# POWER_GEN.net
KiCad netlist of a schematic drawn in Altium Designer
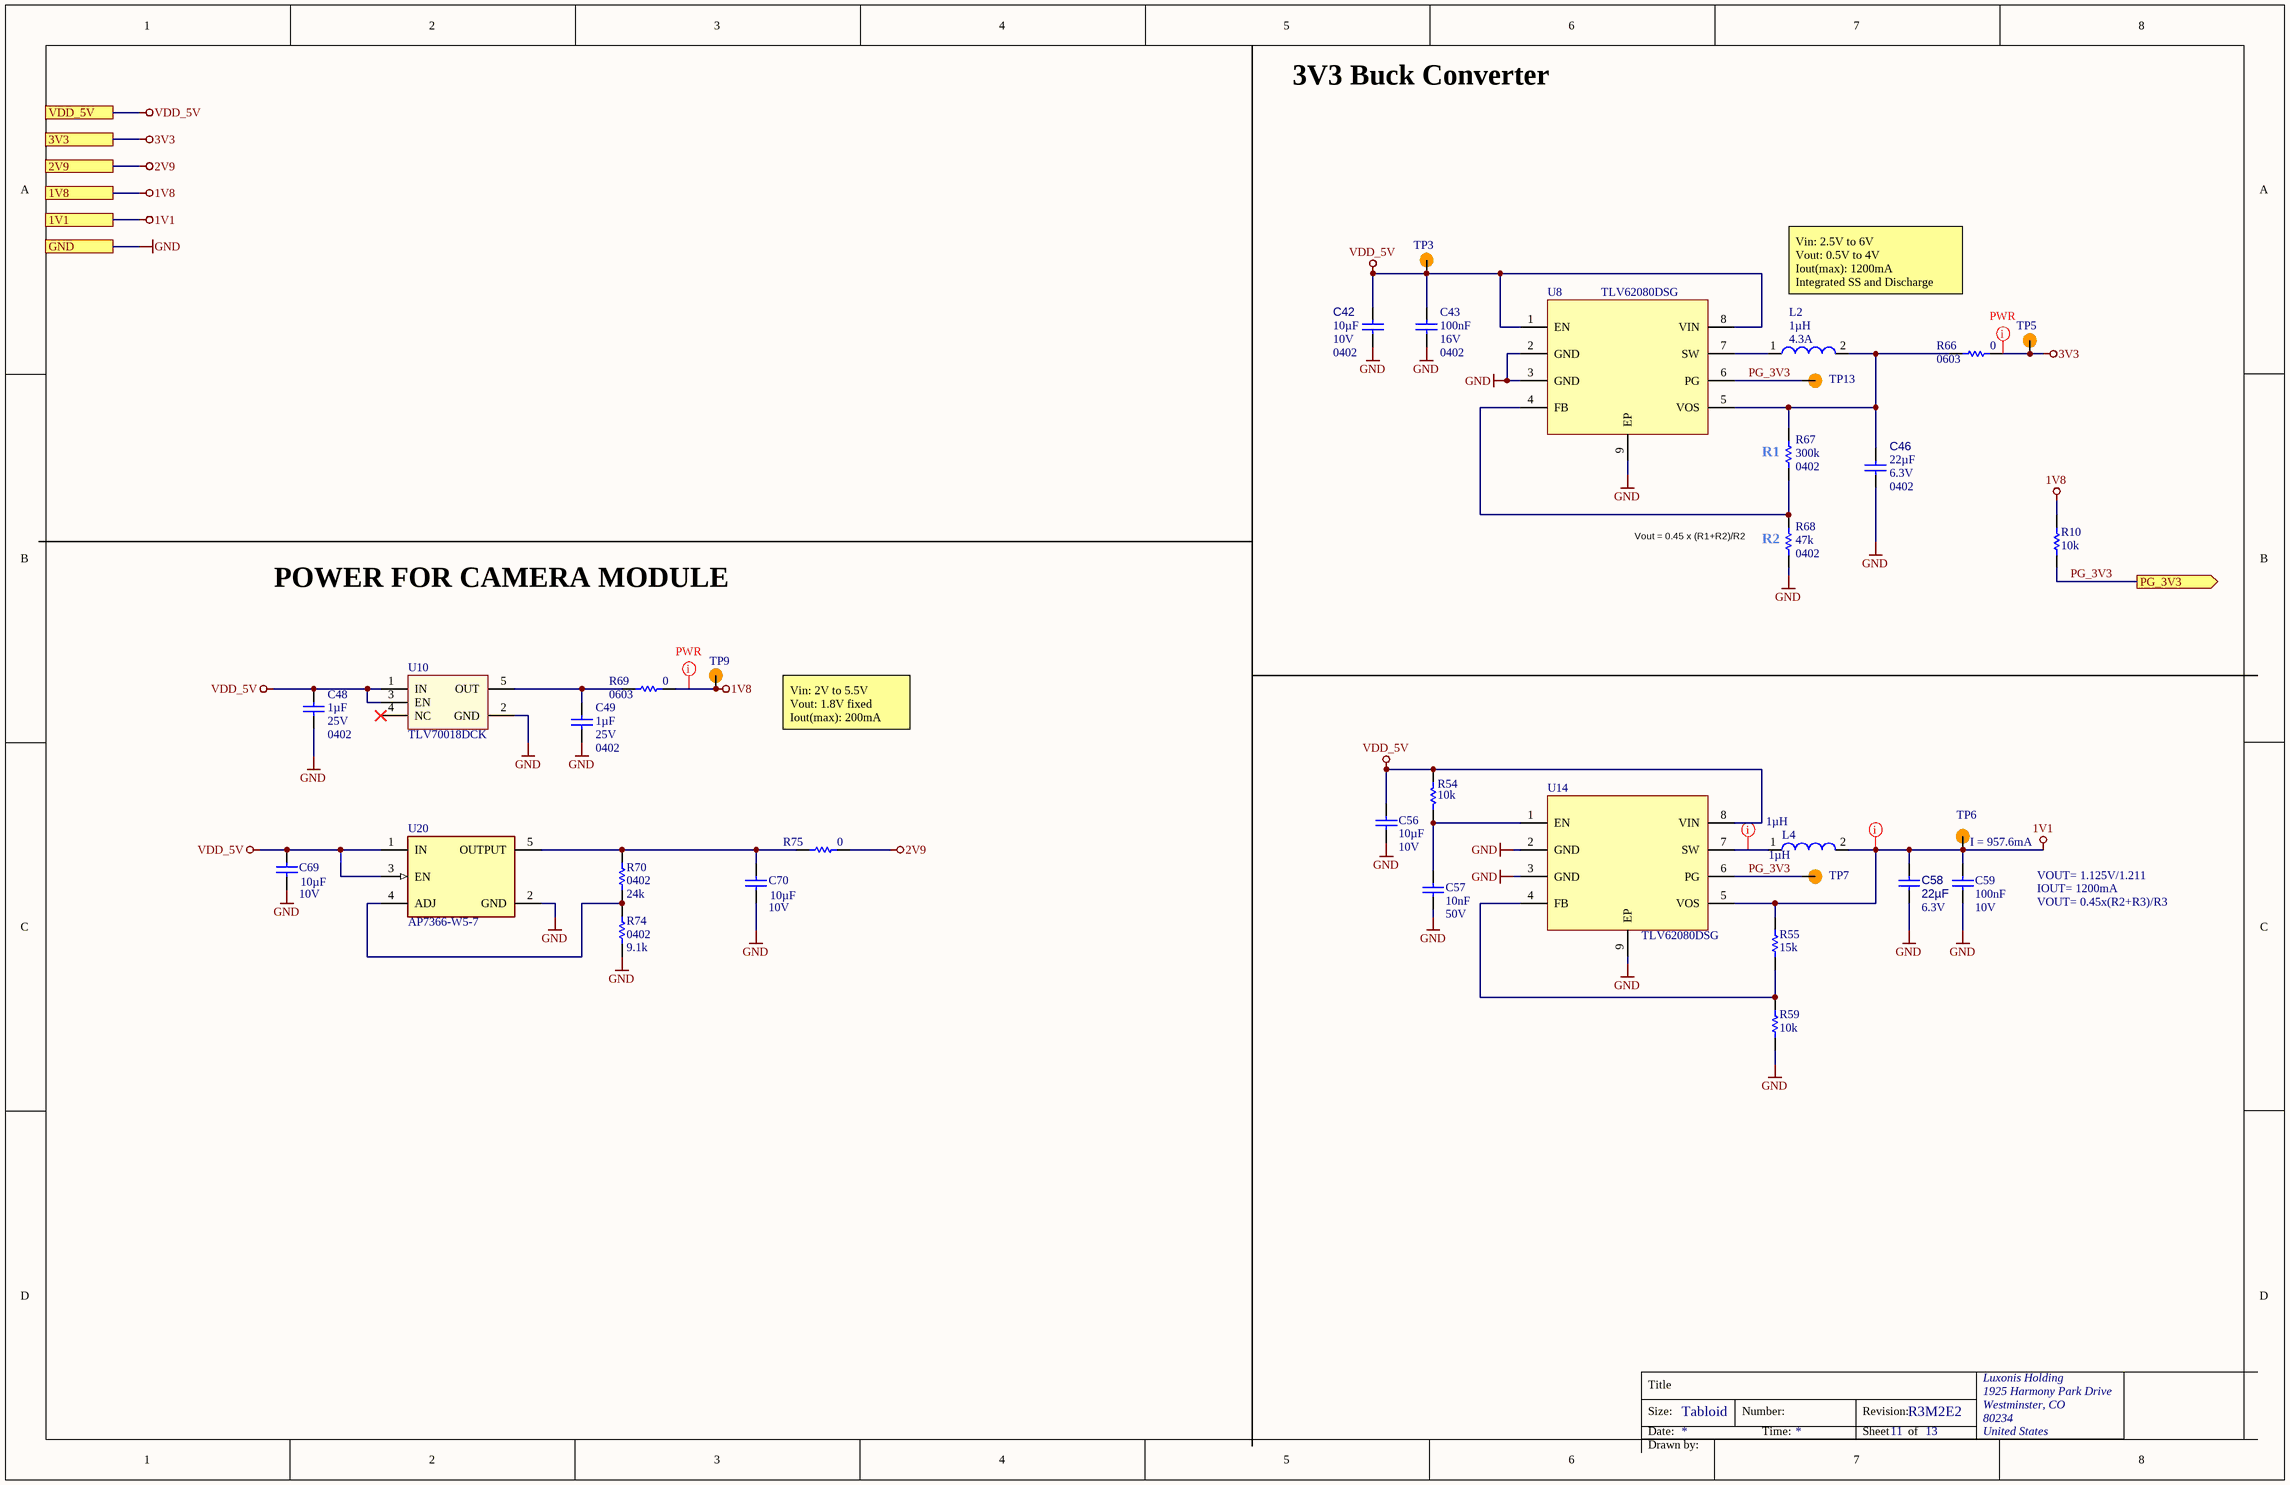
[diagram p0: POWER_GEN.SchDoc]

(export (version "E")
  (design (tool "Eeschema 10.0.6"))
  (components
    (comp (ref "C42")
      (value "10µF")
      (footprint "CAPC0402(1005)60_L")
      (description "CAP CER 10UF 10V X5R 0402 20%")
      (fields
        (field (name "VOLTAGE RATING") "10V")
        (field (name "TOLERANCE") "20%")
        (field (name "CASE/PACKAGE") "0402")
        (field (name "Comment") "GRM155R61A106ME11D")
      )
      (libsource (lib "Luxonis LLC") (part "*"))
    )
    (comp (ref "C43")
      (value "100nF")
      (footprint "CAPC0402(1005)60_N")
      (description "CAP CER 0.1UF 16V X7R 0402 10%")
      (fields
        (field (name "VOLTAGE RATING") "16V")
        (field (name "CASE/PACKAGE") "0402")
        (field (name "TOLERANCE") "10%")
        (field (name "Comment") "CL05B104KO5NFNC")
      )
      (libsource (lib "Luxonis LLC") (part "GRM188R61C475KAAJD"))
    )
    (comp (ref "C46")
      (value "22µF")
      (footprint "CAPC0402(1005)60_L")
      (description "CAP CER 22UF 6.3V X5R 0402 20%")
      (fields
        (field (name "VOLTAGE RATING") "6.3V")
        (field (name "CASE/PACKAGE") "0402")
        (field (name "TOLERANCE") "20%")
        (field (name "Comment") "CL05A226MQ5N6J8")
      )
      (libsource (lib "Luxonis LLC") (part "*"))
    )
    (comp (ref "C48")
      (value "1µF")
      (footprint "CAPC0402(1005)70_N")
      (description "CAP CER 1UF 25V X5R 0402 10%")
      (fields
        (field (name "VOLTAGE RATING") "25V")
        (field (name "CASE/PACKAGE") "0402")
        (field (name "TOLERANCE") "10%")
        (field (name "Comment") "GRM155R61E105KA12D")
      )
      (libsource (lib "Luxonis LLC") (part "GRM188R61C475KAAJD"))
    )
    (comp (ref "C49")
      (value "1µF")
      (footprint "CAPC0402(1005)70_N")
      (description "CAP CER 1UF 25V X5R 0402 10%")
      (fields
        (field (name "VOLTAGE RATING") "25V")
        (field (name "CASE/PACKAGE") "0402")
        (field (name "TOLERANCE") "10%")
        (field (name "Comment") "GRM155R61E105KA12D")
      )
      (libsource (lib "Luxonis LLC") (part "GRM188R61C475KAAJD"))
    )
    (comp (ref "C56")
      (value "10µF")
      (footprint "CAPC0603(1608)100_L")
      (description "CAP CER 10UF 10V X5R 0603 20%")
      (fields (field (name "TOLERANCE") "20%") (field (name "VOLTAGE RATING") "10V"))
      (libsource (lib "Luxonis LLC") (part "LLL153C70G474ME17E"))
    )
    (comp (ref "C57")
      (value "10nF")
      (footprint "CAPC0402(1005)60_L")
      (description "CAP CER 10000PF 50V X7R 0402 10%")
      (fields (field (name "TOLERANCE") "10%") (field (name "VOLTAGE RATING") "50V"))
      (libsource (lib "Luxonis LLC") (part "GRM188R61C475KAAJD"))
    )
    (comp (ref "C58")
      (value "22µF")
      (footprint "CAPC0402(1005)60_L")
      (description "CAP CER 22UF 6.3V X5R 0402 20%")
      (fields (field (name "TOLERANCE") "20%") (field (name "VOLTAGE RATING") "6.3V"))
      (libsource (lib "Luxonis LLC") (part "*"))
    )
    (comp (ref "C59")
      (value "100nF")
      (footprint "CAPC0402(1005)70_L")
      (description "CAP CER 0.1UF 10V X7R 0402 5%")
      (fields (field (name "TOLERANCE") "5%") (field (name "VOLTAGE RATING") "10V"))
      (libsource (lib "Luxonis LLC") (part "GRM188R61C475KAAJD"))
    )
    (comp (ref "C69")
      (value "10µF")
      (footprint "CAPC0603(1608)100_L")
      (description "CAP CER 10UF 10V X5R 0603 20%")
      (fields
        (field (name "TOLERANCE") "20%")
        (field (name "VOLTAGE RATING") "10V")
        (field (name "Comment") "GRM188R61A106ME69D")
      )
      (libsource (lib "Luxonis LLC") (part "LLL153C70G474ME17E"))
    )
    (comp (ref "C70")
      (value "10µF")
      (footprint "CAPC0603(1608)100_L")
      (description "CAP CER 10UF 10V X5R 0603 20%")
      (fields
        (field (name "TOLERANCE") "20%")
        (field (name "VOLTAGE RATING") "10V")
        (field (name "Comment") "GRM188R61A106ME69D")
      )
      (libsource (lib "Luxonis LLC") (part "LLL153C70G474ME17E"))
    )
    (comp (ref "L2")
      (value "1µH")
      (footprint "DFE252012P-1R0M=P2")
      (description "FIXED IND 1UH 3.2A 42 MOHM SMD")
      (fields
        (field (name "MANUFACTURER") "Murata")
        (field (name "MANUFACTURER PART NUMBER") "DFE252012P-1R0M=P2")
        (field (name "CURRENT RATING") "4.3A")
      )
      (libsource (lib "Luxonis LLC") (part "DFE252012P-1R0M=P2"))
    )
    (comp (ref "L4")
      (value "1µH")
      (footprint "DFE252012P-1R0M=P2")
      (description "FIXED IND 1UH 3.2A 42 MOHM SMD")
      (fields
        (field (name "TOLERANCE") "20%")
        (field (name "MANUFACTURER") "Murata")
        (field (name "ALTIUM_VALUE") "1µH")
      )
      (libsource (lib "Luxonis LLC") (part "DFE252012P-1R0M=P2"))
    )
    (comp (ref "R10")
      (value "10k")
      (footprint "RESC0402(1005)_L")
      (description "RES SMD 10K OHM 1% 1/16W 0402")
      (fields (field (name "TOLERANCE") "1%"))
      (libsource (lib "Luxonis LLC") (part "RC0402FR-0722RL_1"))
    )
    (comp (ref "R54")
      (value "10k")
      (footprint "RESC0402(1005)_L")
      (description "RES SMD 10K OHM 1% 1/16W 0402")
      (fields (field (name "TOLERANCE") "1%"))
      (libsource (lib "Luxonis LLC") (part "RC0402FR-0722RL_1"))
    )
    (comp (ref "R55")
      (value "15k")
      (footprint "RESC0402(1005)_L")
      (description "RES SMD 15K OHM 1% 1/16W 0402")
      (fields (field (name "TOLERANCE") "1%"))
      (libsource (lib "Luxonis LLC") (part "Default resistor symbol"))
    )
    (comp (ref "R59")
      (value "10k")
      (footprint "RESC0402(1005)_L")
      (description "RES SMD 10K OHM 1% 1/16W 0402")
      (fields (field (name "TOLERANCE") "1%"))
      (libsource (lib "Luxonis LLC") (part "RC0402FR-0722RL_1"))
    )
    (comp (ref "R66")
      (value "0")
      (footprint "RESC0603(1608)_N")
      (description "RES SMD 0 OHM 5% 1/10W 0603")
      (fields
        (field (name "TOLERANCE") "5%")
        (field (name "CASE/PACKAGE") "0603")
        (field (name "Comment") "CRCW06030000Z0EA")
      )
      (libsource (lib "Luxonis LLC") (part "RC0402FR-0722RL_1"))
    )
    (comp (ref "R67")
      (value "300k")
      (footprint "RESC0402(1005)_N")
      (description "RES SMD 300K OHM 1% 1/16W 0402")
      (fields
        (field (name "CASE/PACKAGE") "0402")
        (field (name "TOLERANCE") "1%")
        (field (name "Comment") "RC0402FR-07300KL")
      )
      (libsource (lib "Luxonis LLC") (part "Default resistor symbol"))
    )
    (comp (ref "R68")
      (value "47k")
      (footprint "RESC0402(1005)_L")
      (description "RES SMD 47K OHM 1% 1/16W 0402")
      (fields
        (field (name "CASE/PACKAGE") "0402")
        (field (name "TOLERANCE") "1%")
        (field (name "Comment") "RC0402FR-0747KL")
      )
      (libsource (lib "Luxonis LLC") (part "Default resistor symbol"))
    )
    (comp (ref "R69")
      (value "0")
      (footprint "RESC0603(1608)_N")
      (description "RES SMD 0 OHM 5% 1/10W 0603")
      (fields
        (field (name "TOLERANCE") "5%")
        (field (name "CASE/PACKAGE") "0603")
        (field (name "Comment") "CRCW06030000Z0EA")
      )
      (libsource (lib "Luxonis LLC") (part "RC0402FR-0722RL_1"))
    )
    (comp (ref "R70")
      (value "24k")
      (footprint "RESC0402(1005)_L")
      (description "RES SMD 24K OHM 1% 1/16W 0402")
      (fields
        (field (name "CASE/PACKAGE") "0402")
        (field (name "TOLERANCE") "1%")
        (field (name "Comment") "RC0402FR-0724KL")
      )
      (libsource (lib "Luxonis LLC") (part "Default resistor symbol"))
    )
    (comp (ref "R74")
      (value "9.1k")
      (footprint "RESC0402(1005)_L")
      (description "RES SMD 9.1K OHM 1% 1/16W 0402")
      (fields
        (field (name "CASE/PACKAGE") "0402")
        (field (name "POWER") "63mW")
        (field (name "TOLERANCE") "1%")
      )
      (libsource (lib "Luxonis LLC") (part "Default resistor symbol"))
    )
    (comp (ref "R75")
      (value "0")
      (footprint "RESC0603(1608)_N")
      (description "RES SMD 0 OHM 5% 1/10W 0603")
      (fields (field (name "TOLERANCE") "5%") (field (name "Comment") "CRCW06030000Z0EA"))
      (libsource (lib "Luxonis LLC") (part "RC0402FR-0722RL_1"))
    )
    (comp (ref "TP3")
      (value "TEST_POINT")
      (footprint "TP075_150_NS")
      (libsource (lib "Luxonis LLC") (part "TEST_POINT"))
    )
    (comp (ref "TP5")
      (value "TEST_POINT")
      (footprint "TP075_150_NS")
      (libsource (lib "Luxonis LLC") (part "TEST_POINT"))
    )
    (comp (ref "TP6")
      (value "TEST_POINT")
      (footprint "TP075_150_NS")
      (libsource (lib "Luxonis LLC") (part "TEST_POINT"))
    )
    (comp (ref "TP7")
      (value "TEST_POINT")
      (footprint "TP075_150_NS")
      (libsource (lib "Luxonis LLC") (part "TEST_POINT"))
    )
    (comp (ref "TP9")
      (value "TEST_POINT")
      (footprint "TP075_150_NS")
      (libsource (lib "Luxonis LLC") (part "TEST_POINT"))
    )
    (comp (ref "TP13")
      (value "TEST_POINT")
      (footprint "TP075_150_NS")
      (libsource (lib "Luxonis LLC") (part "TEST_POINT"))
    )
    (comp (ref "U8")
      (value "TLV62080DSG")
      (footprint "TLV62080DSG")
      (description "IC REG BUCK ADJ 1.2A SYNC 8WSON")
      (libsource (lib "Luxonis LLC") (part "TLV62080DSG"))
    )
    (comp (ref "U10")
      (value "TLV70018DCK")
      (footprint "TLV70018DCK")
      (description "IC REG LINEAR 1.8V 200MA SC70-5 Linear Voltage Regulator IC  1 Output  200mA SC-70-5")
      (libsource (lib "Luxonis LLC") (part "TLV70018DCK"))
    )
    (comp (ref "U14")
      (value "TLV62080DSG")
      (footprint "TLV62080DSG")
      (description "IC REG BUCK ADJ 1.2A SYNC 8WSON")
      (libsource (lib "Luxonis LLC") (part "TLV62080DSG"))
    )
    (comp (ref "U20")
      (value "AP7366-W5-7")
      (footprint "FP-SOT25-MFG")
      (description "Adjustable Positive LDO Regulator, 0.8V Min, 5V Max, PDSO5")
      (libsource (lib "Luxonis LLC") (part "19e870b6970c17930361da943da2777"))
    )
  )
  (nets
    (net (code "1") (name "/PG_3V3") (class "Default")
      (node (ref "R10") (pin "1") (pinfunction "1_1") (pintype "passive"))
      (node (ref "TP13") (pin "1") (pintype "passive"))
      (node (ref "TP7") (pin "1") (pintype "passive"))
      (node (ref "U14") (pin "6") (pinfunction "PG_6") (pintype "passive"))
      (node (ref "U8") (pin "6") (pinfunction "PG_6") (pintype "passive"))
    )
    (net (code "2") (name "1V1") (class "Default")
      (node (ref "C58") (pin "2") (pinfunction "2_2") (pintype "passive"))
      (node (ref "C59") (pin "2") (pinfunction "2_2") (pintype "passive"))
      (node (ref "L4") (pin "2") (pinfunction "2_2") (pintype "passive"))
      (node (ref "R55") (pin "2") (pinfunction "2_2") (pintype "passive"))
      (node (ref "TP6") (pin "1") (pintype "passive"))
      (node (ref "U14") (pin "5") (pinfunction "VOS_5") (pintype "passive"))
    )
    (net (code "3") (name "1V8") (class "Default")
      (node (ref "R10") (pin "2") (pinfunction "2_2") (pintype "passive"))
      (node (ref "R69") (pin "2") (pinfunction "2_2") (pintype "passive"))
      (node (ref "TP9") (pin "1") (pintype "passive"))
    )
    (net (code "4") (name "2V9") (class "Default")
      (node (ref "R75") (pin "2") (pinfunction "2_2") (pintype "passive"))
    )
    (net (code "5") (name "3V3") (class "Default")
      (node (ref "R66") (pin "2") (pinfunction "2_2") (pintype "passive"))
      (node (ref "TP5") (pin "1") (pintype "passive"))
    )
    (net (code "6") (name "GND") (class "Default")
      (node (ref "C42") (pin "1") (pinfunction "1_1") (pintype "passive"))
      (node (ref "C43") (pin "1") (pinfunction "1_1") (pintype "passive"))
      (node (ref "C46") (pin "1") (pinfunction "1_1") (pintype "passive"))
      (node (ref "C48") (pin "1") (pinfunction "1_1") (pintype "passive"))
      (node (ref "C49") (pin "1") (pinfunction "1_1") (pintype "passive"))
      (node (ref "C56") (pin "1") (pinfunction "1_1") (pintype "passive"))
      (node (ref "C57") (pin "1") (pinfunction "1_1") (pintype "passive"))
      (node (ref "C58") (pin "1") (pinfunction "1_1") (pintype "passive"))
      (node (ref "C59") (pin "1") (pinfunction "1_1") (pintype "passive"))
      (node (ref "C69") (pin "1") (pinfunction "1_1") (pintype "passive"))
      (node (ref "C70") (pin "1") (pinfunction "1_1") (pintype "passive"))
      (node (ref "R59") (pin "1") (pinfunction "1_1") (pintype "passive"))
      (node (ref "R68") (pin "1") (pinfunction "1_1") (pintype "passive"))
      (node (ref "R74") (pin "1") (pinfunction "1_1") (pintype "passive"))
      (node (ref "U10") (pin "2") (pinfunction "GND_2") (pintype "passive"))
      (node (ref "U14") (pin "2") (pinfunction "GND_2") (pintype "passive"))
      (node (ref "U14") (pin "3") (pinfunction "GND_3") (pintype "passive"))
      (node (ref "U14") (pin "9") (pinfunction "EP_9") (pintype "passive"))
      (node (ref "U20") (pin "2") (pinfunction "GND_2") (pintype "power_in"))
      (node (ref "U8") (pin "2") (pinfunction "GND_2") (pintype "passive"))
      (node (ref "U8") (pin "3") (pinfunction "GND_3") (pintype "passive"))
      (node (ref "U8") (pin "9") (pinfunction "EP_9") (pintype "passive"))
    )
    (net (code "7") (name "Net-(U8-FB)") (class "Default")
      (node (ref "R67") (pin "1") (pinfunction "1_1") (pintype "passive"))
      (node (ref "R68") (pin "2") (pinfunction "2_2") (pintype "passive"))
      (node (ref "U8") (pin "4") (pinfunction "FB_4") (pintype "passive"))
    )
    (net (code "8") (name "Net-(U8-SW)") (class "Default")
      (node (ref "L2") (pin "1") (pinfunction "1_1") (pintype "passive"))
      (node (ref "U8") (pin "7") (pinfunction "SW_7") (pintype "passive"))
    )
    (net (code "9") (name "Net-(U8-VOS)") (class "Default")
      (node (ref "C46") (pin "2") (pinfunction "2_2") (pintype "passive"))
      (node (ref "L2") (pin "2") (pinfunction "2_2") (pintype "passive"))
      (node (ref "R66") (pin "1") (pinfunction "1_1") (pintype "passive"))
      (node (ref "R67") (pin "2") (pinfunction "2_2") (pintype "passive"))
      (node (ref "U8") (pin "5") (pinfunction "VOS_5") (pintype "passive"))
    )
    (net (code "10") (name "Net-(U10-OUT)") (class "Default")
      (node (ref "C49") (pin "2") (pinfunction "2_2") (pintype "passive"))
      (node (ref "R69") (pin "1") (pinfunction "1_1") (pintype "passive"))
      (node (ref "U10") (pin "5") (pinfunction "OUT_5") (pintype "passive"))
    )
    (net (code "11") (name "Net-(U14-EN)") (class "Default")
      (node (ref "C57") (pin "2") (pinfunction "2_2") (pintype "passive"))
      (node (ref "R54") (pin "1") (pinfunction "1_1") (pintype "passive"))
      (node (ref "U14") (pin "1") (pinfunction "EN_1") (pintype "passive"))
    )
    (net (code "12") (name "Net-(U14-FB)") (class "Default")
      (node (ref "R55") (pin "1") (pinfunction "1_1") (pintype "passive"))
      (node (ref "R59") (pin "2") (pinfunction "2_2") (pintype "passive"))
      (node (ref "U14") (pin "4") (pinfunction "FB_4") (pintype "passive"))
    )
    (net (code "13") (name "Net-(U14-SW)") (class "Default")
      (node (ref "L4") (pin "1") (pinfunction "1_1") (pintype "passive"))
      (node (ref "U14") (pin "7") (pinfunction "SW_7") (pintype "passive"))
    )
    (net (code "14") (name "Net-(U20-ADJ)") (class "Default")
      (node (ref "R70") (pin "1") (pinfunction "1_1") (pintype "passive"))
      (node (ref "R74") (pin "2") (pinfunction "2_2") (pintype "passive"))
      (node (ref "U20") (pin "4") (pinfunction "ADJ_4") (pintype "passive"))
    )
    (net (code "15") (name "Net-(U20-OUTPUT)") (class "Default")
      (node (ref "C70") (pin "2") (pinfunction "2_2") (pintype "passive"))
      (node (ref "R70") (pin "2") (pinfunction "2_2") (pintype "passive"))
      (node (ref "R75") (pin "1") (pinfunction "1_1") (pintype "passive"))
      (node (ref "U20") (pin "5") (pinfunction "OUTPUT_5") (pintype "power_in"))
    )
    (net (code "16") (name "VDD_5V") (class "Default")
      (node (ref "C42") (pin "2") (pinfunction "2_2") (pintype "passive"))
      (node (ref "C43") (pin "2") (pinfunction "2_2") (pintype "passive"))
      (node (ref "C48") (pin "2") (pinfunction "2_2") (pintype "passive"))
      (node (ref "C56") (pin "2") (pinfunction "2_2") (pintype "passive"))
      (node (ref "C69") (pin "2") (pinfunction "2_2") (pintype "passive"))
      (node (ref "R54") (pin "2") (pinfunction "2_2") (pintype "passive"))
      (node (ref "TP3") (pin "1") (pintype "passive"))
      (node (ref "U10") (pin "1") (pinfunction "IN_1") (pintype "passive"))
      (node (ref "U10") (pin "3") (pinfunction "EN_3") (pintype "passive"))
      (node (ref "U14") (pin "8") (pinfunction "VIN_8") (pintype "passive"))
      (node (ref "U20") (pin "1") (pinfunction "IN_1") (pintype "power_in"))
      (node (ref "U20") (pin "3") (pinfunction "EN_3") (pintype "input"))
      (node (ref "U8") (pin "1") (pinfunction "EN_1") (pintype "passive"))
      (node (ref "U8") (pin "8") (pinfunction "VIN_8") (pintype "passive"))
    )
    (net (code "17") (name "unconnected-(U10-NC-Pad4)") (class "Default")
      (node (ref "U10") (pin "4") (pinfunction "NC_4") (pintype "passive+no_connect"))
    )
  )
)
